# relay.net
KiCad netlist of a schematic drawn in EAGLE
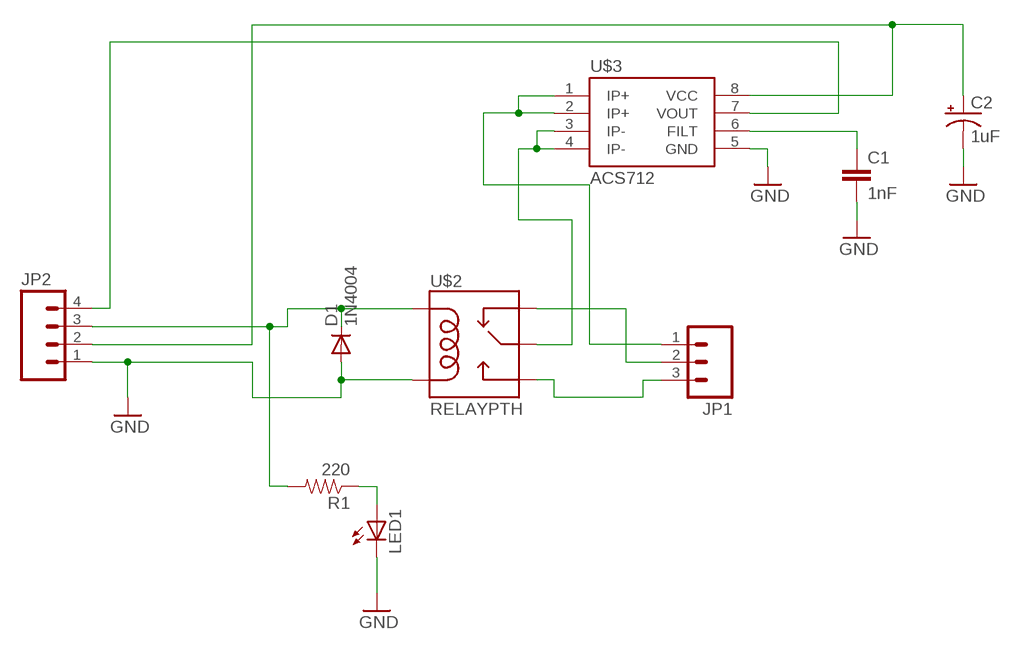
[diagram p0: schematic, sheet 1]

(export (version "E")
  (design (tool "Eeschema 10.0.6"))
  (components
    (comp (ref "C1")
      (value "1nF")
      (footprint "eagle-import:CAP-PTH-SMALL-KIT")
      (libsource (lib "eagle-import") (part "CAPKIT"))
    )
    (comp (ref "C2")
      (value "1uF")
      (footprint "eagle-import:CPOL-RADIAL-10UF-25V")
      (libsource (lib "eagle-import") (part "CAP_POLPTH2"))
    )
    (comp (ref "D1")
      (value "1N4004")
      (footprint "eagle-import:DO41-10")
      (libsource (lib "eagle-import") (part "1N4004"))
    )
    (comp (ref "JP1")
      (value "M03SCREW")
      (footprint "eagle-import:SCREWTERMINAL-3.5MM-3")
      (libsource (lib "eagle-import") (part "M03SCREW"))
    )
    (comp (ref "JP2")
      (value "M04PTH")
      (footprint "eagle-import:1X04")
      (libsource (lib "eagle-import") (part "M04PTH"))
    )
    (comp (ref "LED1")
      (value "LED3MM")
      (footprint "eagle-import:LED3MM")
      (libsource (lib "eagle-import") (part "LED3MM"))
    )
    (comp (ref "R1")
      (value "220")
      (footprint "eagle-import:AXIAL-0.3")
      (libsource (lib "eagle-import") (part "RESISTORAXIAL-0.3"))
    )
    (comp (ref "U$2")
      (value "RELAYPTH")
      (footprint "eagle-import:RELAY-G5Q")
      (libsource (lib "eagle-import") (part "RELAYPTH"))
    )
    (comp (ref "U$3")
      (value "ACS712")
      (footprint "eagle-import:SO08")
      (libsource (lib "eagle-import") (part "ACS712"))
    )
  )
  (nets
    (net (code "1") (name "GND") (class "Default")
      (node (ref "C1") (pin "2") (pinfunction "2_2") (pintype "passive"))
      (node (ref "C2") (pin "2") (pinfunction "-_2") (pintype "passive"))
      (node (ref "D1") (pin "A") (pinfunction "A_A") (pintype "passive"))
      (node (ref "JP2") (pin "1") (pinfunction "1_1") (pintype "passive"))
      (node (ref "LED1") (pin "K") (pinfunction "C_K") (pintype "passive"))
      (node (ref "U$2") (pin "1") (pinfunction "COIL2_1") (pintype "bidirectional"))
      (node (ref "U$3") (pin "5") (pinfunction "GND_5") (pintype "bidirectional"))
    )
    (net (code "2") (name "Net-(C2-+)") (class "Default")
      (node (ref "C2") (pin "1") (pinfunction "+_1") (pintype "passive"))
      (node (ref "JP2") (pin "2") (pinfunction "2_2") (pintype "passive"))
      (node (ref "U$3") (pin "8") (pinfunction "VCC_8") (pintype "bidirectional"))
    )
    (net (code "3") (name "Net-(JP1-Pad1)") (class "Default")
      (node (ref "JP1") (pin "1") (pinfunction "1_1") (pintype "passive"))
      (node (ref "U$3") (pin "1") (pinfunction "IP+_1") (pintype "bidirectional"))
      (node (ref "U$3") (pin "2") (pinfunction "IP+_2") (pintype "bidirectional"))
    )
    (net (code "4") (name "Net-(R1-1)") (class "Default")
      (node (ref "LED1") (pin "A") (pinfunction "A_A") (pintype "passive"))
      (node (ref "R1") (pin "P$1") (pinfunction "1_P$1") (pintype "passive"))
    )
    (net (code "5") (name "Net-(R1-2)") (class "Default")
      (node (ref "D1") (pin "C") (pinfunction "C_C") (pintype "passive"))
      (node (ref "JP2") (pin "3") (pinfunction "3_3") (pintype "passive"))
      (node (ref "R1") (pin "P$2") (pinfunction "2_P$2") (pintype "passive"))
      (node (ref "U$2") (pin "5") (pinfunction "COIL1_5") (pintype "bidirectional"))
    )
    (net (code "6") (name "Net-(U$2-MAIN)") (class "Default")
      (node (ref "U$2") (pin "2") (pinfunction "MAIN_2") (pintype "bidirectional"))
      (node (ref "U$3") (pin "3") (pinfunction "IP-_3") (pintype "bidirectional"))
      (node (ref "U$3") (pin "4") (pinfunction "IP-_4") (pintype "bidirectional"))
    )
    (net (code "7") (name "Net-(U$2-NC)") (class "Default")
      (node (ref "JP1") (pin "2") (pinfunction "2_2") (pintype "passive"))
      (node (ref "U$2") (pin "4") (pinfunction "NC_4") (pintype "bidirectional"))
    )
    (net (code "8") (name "Net-(U$2-NO)") (class "Default")
      (node (ref "JP1") (pin "3") (pinfunction "3_3") (pintype "passive"))
      (node (ref "U$2") (pin "3") (pinfunction "NO_3") (pintype "bidirectional"))
    )
    (net (code "9") (name "Net-(U$3-FILT)") (class "Default")
      (node (ref "C1") (pin "1") (pinfunction "1_1") (pintype "passive"))
      (node (ref "U$3") (pin "6") (pinfunction "FILT_6") (pintype "bidirectional"))
    )
    (net (code "10") (name "Net-(U$3-VOUT)") (class "Default")
      (node (ref "JP2") (pin "4") (pinfunction "4_4") (pintype "passive"))
      (node (ref "U$3") (pin "7") (pinfunction "VOUT_7") (pintype "bidirectional"))
    )
  )
)
